# User_Input.net
KiCad netlist of a schematic drawn in EAGLE
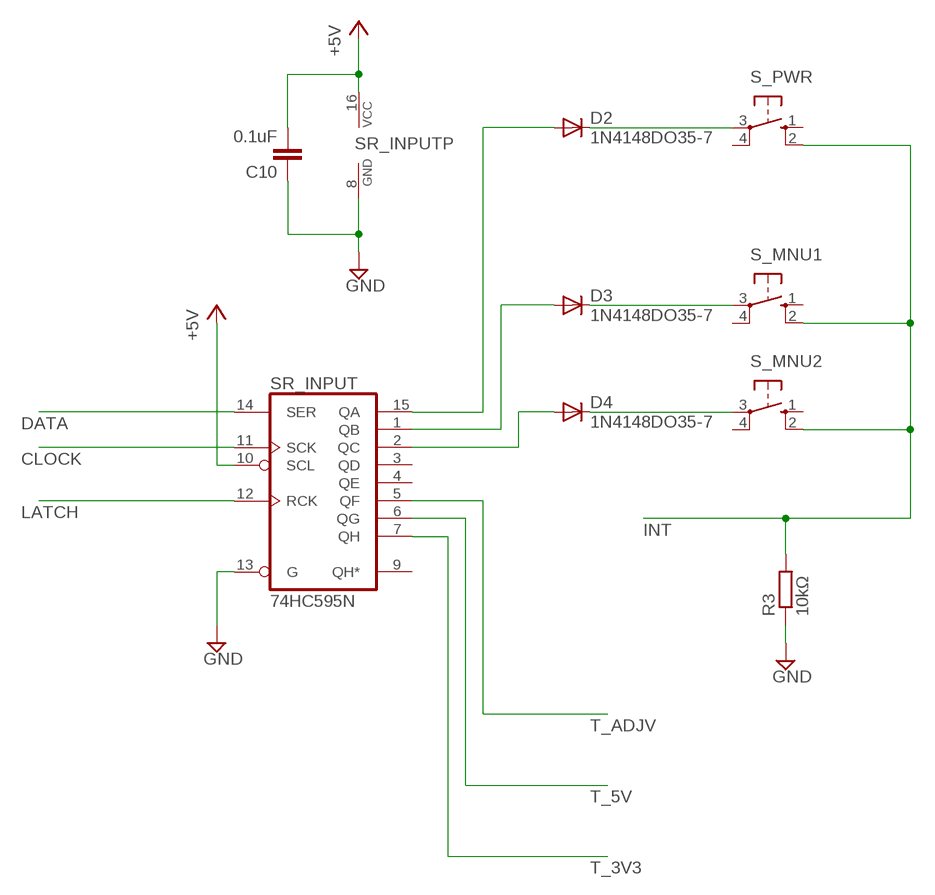
[diagram p0: schematic, sheet 1]

(export (version "E")
  (design (tool "Eeschema 10.0.6"))
  (components
    (comp (ref "C10")
      (value "0.1uF")
      (footprint "eagle-import:C025-025X050")
      (libsource (lib "eagle-import") (part "C-EU025-025X050"))
    )
    (comp (ref "D2")
      (value "1N4148DO35-7")
      (footprint "eagle-import:DO35-7")
      (libsource (lib "eagle-import") (part "1N4148DO35-7"))
    )
    (comp (ref "D3")
      (value "1N4148DO35-7")
      (footprint "eagle-import:DO35-7")
      (libsource (lib "eagle-import") (part "1N4148DO35-7"))
    )
    (comp (ref "D4")
      (value "1N4148DO35-7")
      (footprint "eagle-import:DO35-7")
      (libsource (lib "eagle-import") (part "1N4148DO35-7"))
    )
    (comp (ref "R3")
      (value "10kΩ")
      (footprint "eagle-import:0207_10")
      (libsource (lib "eagle-import") (part "R-EU_0207/10"))
    )
    (comp (ref "SR_INPUT")
      (value "74HC595N")
      (footprint "eagle-import:DIL16")
      (libsource (lib "eagle-import") (part "74595NHC"))
    )
    (comp (ref "S_MNU1")
      (value "10-XX")
      (footprint "eagle-import:B3F-10XX")
      (fields (field (name "MPN") "B3F-1000"))
      (libsource (lib "eagle-import") (part "10-XX"))
    )
    (comp (ref "S_MNU2")
      (value "10-XX")
      (footprint "eagle-import:B3F-10XX")
      (fields (field (name "MPN") "B3F-1000"))
      (libsource (lib "eagle-import") (part "10-XX"))
    )
    (comp (ref "S_PWR")
      (value "10-XX")
      (footprint "eagle-import:B3F-10XX")
      (fields (field (name "MPN") "B3F-1000"))
      (libsource (lib "eagle-import") (part "10-XX"))
    )
  )
  (nets
    (net (code "1") (name "+5V") (class "Default")
      (node (ref "C10") (pin "2") (pinfunction "2_2") (pintype "passive"))
      (node (ref "SR_INPUT") (pin "10") (pinfunction "SCL_10") (pintype "input"))
      (node (ref "SR_INPUT") (pin "16") (pinfunction "VCC_16") (pintype "power_in"))
    )
    (net (code "2") (name "/CLOCK") (class "Default")
      (node (ref "SR_INPUT") (pin "11") (pinfunction "SCK_11") (pintype "input"))
    )
    (net (code "3") (name "/DATA") (class "Default")
      (node (ref "SR_INPUT") (pin "14") (pinfunction "SER_14") (pintype "input"))
    )
    (net (code "4") (name "/INT") (class "Default")
      (node (ref "R3") (pin "2") (pinfunction "2_2") (pintype "passive"))
      (node (ref "S_MNU1") (pin "2") (pinfunction "S1_2") (pintype "passive"))
      (node (ref "S_MNU2") (pin "2") (pinfunction "S1_2") (pintype "passive"))
      (node (ref "S_PWR") (pin "2") (pinfunction "S1_2") (pintype "passive"))
    )
    (net (code "5") (name "/LATCH") (class "Default")
      (node (ref "SR_INPUT") (pin "12") (pinfunction "RCK_12") (pintype "input"))
    )
    (net (code "6") (name "/T_3V3") (class "Default")
      (node (ref "SR_INPUT") (pin "7") (pinfunction "QH_7") (pintype "tri_state"))
    )
    (net (code "7") (name "/T_5V") (class "Default")
      (node (ref "SR_INPUT") (pin "6") (pinfunction "QG_6") (pintype "tri_state"))
    )
    (net (code "8") (name "/T_ADJV") (class "Default")
      (node (ref "SR_INPUT") (pin "5") (pinfunction "QF_5") (pintype "tri_state"))
    )
    (net (code "9") (name "GND") (class "Default")
      (node (ref "C10") (pin "1") (pinfunction "1_1") (pintype "passive"))
      (node (ref "R3") (pin "1") (pinfunction "1_1") (pintype "passive"))
      (node (ref "SR_INPUT") (pin "13") (pinfunction "G_13") (pintype "input"))
      (node (ref "SR_INPUT") (pin "8") (pinfunction "GND_8") (pintype "power_in"))
    )
    (net (code "10") (name "Net-(SR_INPUTA-QA)") (class "Default")
      (node (ref "D2") (pin "A") (pinfunction "A_A") (pintype "passive"))
      (node (ref "SR_INPUT") (pin "15") (pinfunction "QA_15") (pintype "tri_state"))
    )
    (net (code "11") (name "Net-(SR_INPUTA-QB)") (class "Default")
      (node (ref "D3") (pin "A") (pinfunction "A_A") (pintype "passive"))
      (node (ref "SR_INPUT") (pin "1") (pinfunction "QB_1") (pintype "tri_state"))
    )
    (net (code "12") (name "Net-(SR_INPUTA-QC)") (class "Default")
      (node (ref "D4") (pin "A") (pinfunction "A_A") (pintype "passive"))
      (node (ref "SR_INPUT") (pin "2") (pinfunction "QC_2") (pintype "tri_state"))
    )
    (net (code "13") (name "Net-(S_MNU1-P)") (class "Default")
      (node (ref "D3") (pin "C") (pinfunction "C_C") (pintype "passive"))
      (node (ref "S_MNU1") (pin "3") (pinfunction "P_3") (pintype "passive"))
    )
    (net (code "14") (name "Net-(S_MNU2-P)") (class "Default")
      (node (ref "D4") (pin "C") (pinfunction "C_C") (pintype "passive"))
      (node (ref "S_MNU2") (pin "3") (pinfunction "P_3") (pintype "passive"))
    )
    (net (code "15") (name "Net-(S_PWR-P)") (class "Default")
      (node (ref "D2") (pin "C") (pinfunction "C_C") (pintype "passive"))
      (node (ref "S_PWR") (pin "3") (pinfunction "P_3") (pintype "passive"))
    )
    (net (code "16") (name "unconnected-(SR_INPUTA-QD-Pad3)") (class "Default")
      (node (ref "SR_INPUT") (pin "3") (pinfunction "QD_3") (pintype "tri_state"))
    )
    (net (code "17") (name "unconnected-(SR_INPUTA-QE-Pad4)") (class "Default")
      (node (ref "SR_INPUT") (pin "4") (pinfunction "QE_4") (pintype "tri_state"))
    )
    (net (code "18") (name "unconnected-(SR_INPUTA-QH*-Pad9)") (class "Default")
      (node (ref "SR_INPUT") (pin "9") (pinfunction "QH*_9") (pintype "tri_state"))
    )
    (net (code "19") (name "unconnected-(S_MNU1-P1-Pad4)") (class "Default")
      (node (ref "S_MNU1") (pin "4") (pinfunction "P1_4") (pintype "passive"))
    )
    (net (code "20") (name "unconnected-(S_MNU1-S-Pad1)") (class "Default")
      (node (ref "S_MNU1") (pin "1") (pinfunction "S_1") (pintype "passive"))
    )
    (net (code "21") (name "unconnected-(S_MNU2-P1-Pad4)") (class "Default")
      (node (ref "S_MNU2") (pin "4") (pinfunction "P1_4") (pintype "passive"))
    )
    (net (code "22") (name "unconnected-(S_MNU2-S-Pad1)") (class "Default")
      (node (ref "S_MNU2") (pin "1") (pinfunction "S_1") (pintype "passive"))
    )
    (net (code "23") (name "unconnected-(S_PWR-P1-Pad4)") (class "Default")
      (node (ref "S_PWR") (pin "4") (pinfunction "P1_4") (pintype "passive"))
    )
    (net (code "24") (name "unconnected-(S_PWR-S-Pad1)") (class "Default")
      (node (ref "S_PWR") (pin "1") (pinfunction "S_1") (pintype "passive"))
    )
  )
)
